# Mixer.net
KiCad netlist of a schematic drawn in Altium Designer
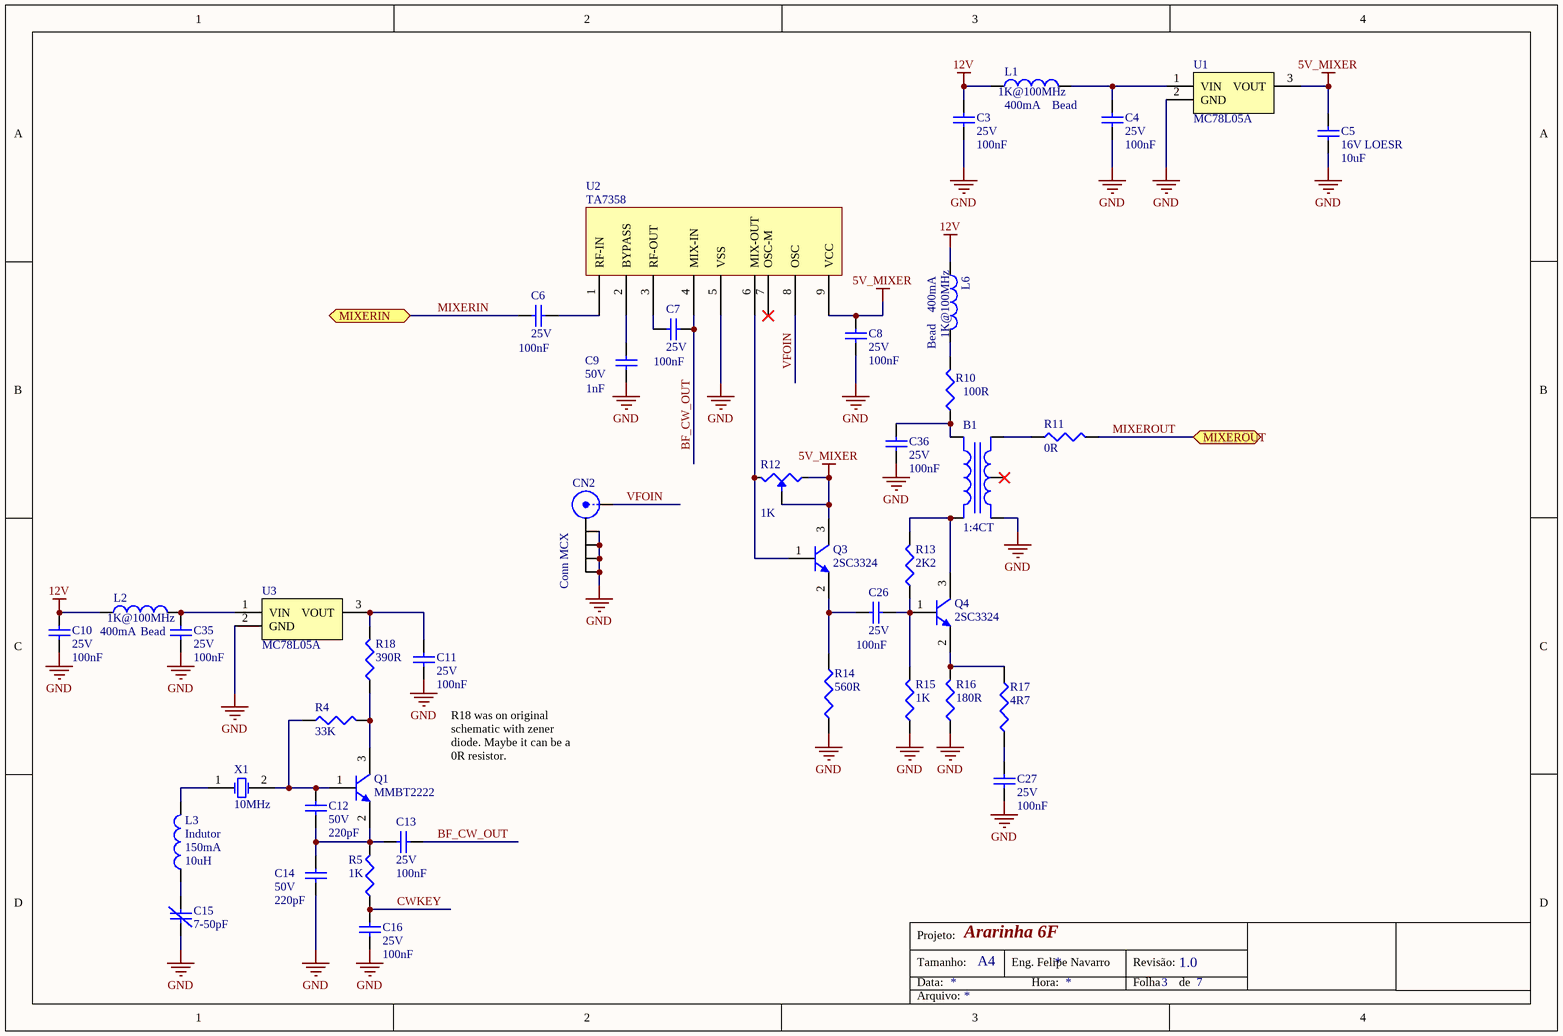
[diagram p0: Mixer.SchDoc]

(export (version "E")
  (design (tool "Eeschema 10.0.6"))
  (components
    (comp (ref "B1")
      (value "1:4CT")
      (footprint "CX2047LANL")
      (description "Balun 4CT:1")
      (libsource (lib "NavarroIND") (part "BALUN CX2047LANL"))
    )
    (comp (ref "C3")
      (value "100nF")
      (footprint "CC0603")
      (description "Capacitor (Semiconductor SIM Model)")
      (fields (field (name "TENSÃO") "25V") (field (name "Comment") "Capacitor Cerâmico"))
      (libsource (lib "NavarroCAP") (part "Cap 100nF 25V 0603 X7R"))
    )
    (comp (ref "C4")
      (value "100nF")
      (footprint "CC0603")
      (description "Capacitor (Semiconductor SIM Model)")
      (fields (field (name "TENSÃO") "25V") (field (name "Comment") "Capacitor Cerâmico"))
      (libsource (lib "NavarroCAP") (part "Cap 100nF 25V 0603 X7R"))
    )
    (comp (ref "C5")
      (value "10uF")
      (footprint "CC0805")
      (description "Capacitor (Semiconductor SIM Model)")
      (fields (field (name "TENSÃO") "16V LOESR") (field (name "Comment") "Capacitor Cerâmico"))
      (libsource (lib "NavarroCAP") (part "Cap 10uF 16V 0805 X6S LOESR"))
    )
    (comp (ref "C6")
      (value "100nF")
      (footprint "CC0603")
      (description "Capacitor (Semiconductor SIM Model)")
      (fields (field (name "TENSÃO") "25V") (field (name "Comment") "Capacitor Cerâmico"))
      (libsource (lib "NavarroCAP") (part "Cap 100nF 25V 0603 X7R"))
    )
    (comp (ref "C7")
      (value "100nF")
      (footprint "CC0603")
      (description "Capacitor (Semiconductor SIM Model)")
      (fields (field (name "TENSÃO") "25V") (field (name "Comment") "Capacitor Cerâmico"))
      (libsource (lib "NavarroCAP") (part "Cap 100nF 25V 0603 X7R"))
    )
    (comp (ref "C8")
      (value "100nF")
      (footprint "CC0603")
      (description "Capacitor (Semiconductor SIM Model)")
      (fields (field (name "TENSÃO") "25V") (field (name "Comment") "Capacitor Cerâmico"))
      (libsource (lib "NavarroCAP") (part "Cap 100nF 25V 0603 X7R"))
    )
    (comp (ref "C9")
      (value "1nF")
      (footprint "CC0603")
      (description "Capacitor (Semiconductor SIM Model)")
      (fields (field (name "TENSÃO") "50V") (field (name "Comment") "Capacitor Cerâmico"))
      (libsource (lib "NavarroCAP") (part "Cap 1nF 50V 0603 NP0"))
    )
    (comp (ref "C10")
      (value "100nF")
      (footprint "CC0603")
      (description "Capacitor (Semiconductor SIM Model)")
      (fields (field (name "TENSÃO") "25V") (field (name "Comment") "Capacitor Cerâmico"))
      (libsource (lib "NavarroCAP") (part "Cap 100nF 25V 0603 X7R"))
    )
    (comp (ref "C11")
      (value "100nF")
      (footprint "CC0603")
      (description "Capacitor (Semiconductor SIM Model)")
      (fields (field (name "TENSÃO") "25V") (field (name "Comment") "Capacitor Cerâmico"))
      (libsource (lib "NavarroCAP") (part "Cap 100nF 25V 0603 X7R"))
    )
    (comp (ref "C12")
      (value "220pF")
      (footprint "CC0603")
      (description "Capacitor (Semiconductor SIM Model)")
      (fields (field (name "TENSÃO") "50V") (field (name "Comment") "Capacitor Cerâmico"))
      (libsource (lib "NavarroCAP") (part "Cap 220pF 50V 0603 NP0"))
    )
    (comp (ref "C13")
      (value "100nF")
      (footprint "CC0603")
      (description "Capacitor (Semiconductor SIM Model)")
      (fields (field (name "TENSÃO") "25V") (field (name "Comment") "Capacitor Cerâmico"))
      (libsource (lib "NavarroCAP") (part "Cap 2.2pf 50V 0603 C0G"))
    )
    (comp (ref "C14")
      (value "220pF")
      (footprint "CC0603")
      (description "Capacitor (Semiconductor SIM Model)")
      (fields (field (name "TENSÃO") "50V") (field (name "Comment") "Capacitor Cerâmico"))
      (libsource (lib "NavarroCAP") (part "Cap 220pF 50V 0603 NP0"))
    )
    (comp (ref "C15")
      (value "7-50pF")
      (footprint "MURATA TZB4")
      (description "Capacitor (Semiconductor SIM Model)")
      (fields (field (name "Comment") "Trimmer"))
      (libsource (lib "NavarroCAP") (part "Trimmer 7-50pF 50V TZB4-BB"))
    )
    (comp (ref "C16")
      (value "100nF")
      (footprint "CC0603")
      (description "Capacitor (Semiconductor SIM Model)")
      (fields (field (name "TENSÃO") "25V") (field (name "Comment") "Capacitor Cerâmico"))
      (libsource (lib "NavarroCAP") (part "Cap 100nF 25V 0603 X7R"))
    )
    (comp (ref "C26")
      (value "100nF")
      (footprint "CC0603")
      (description "Capacitor (Semiconductor SIM Model)")
      (fields (field (name "TENSÃO") "25V") (field (name "Comment") "Capacitor Cerâmico"))
      (libsource (lib "NavarroCAP") (part "Cap 100nF 25V 0603 X7R"))
    )
    (comp (ref "C27")
      (value "100nF")
      (footprint "CC0603")
      (description "Capacitor (Semiconductor SIM Model)")
      (fields (field (name "TENSÃO") "25V") (field (name "Comment") "Capacitor Cerâmico"))
      (libsource (lib "NavarroCAP") (part "Cap 100nF 25V 0603 X7R"))
    )
    (comp (ref "C35")
      (value "100nF")
      (footprint "CC0603")
      (description "Capacitor (Semiconductor SIM Model)")
      (fields (field (name "TENSÃO") "25V") (field (name "Comment") "Capacitor Cerâmico"))
      (libsource (lib "NavarroCAP") (part "Cap 100nF 25V 0603 X7R"))
    )
    (comp (ref "C36")
      (value "100nF")
      (footprint "CC0603")
      (description "Capacitor (Semiconductor SIM Model)")
      (fields (field (name "TENSÃO") "25V") (field (name "Comment") "Capacitor Cerâmico"))
      (libsource (lib "NavarroCAP") (part "Cap 100nF 25V 0603 X7R"))
    )
    (comp (ref "CN2")
      (value "Conn MCX")
      (footprint "CONN MCX MOLEX")
      (description "Conector MCX")
      (libsource (lib "NavarroCON") (part "Conn MCX"))
    )
    (comp (ref "L1")
      (value "Bead")
      (footprint "CC0603")
      (fields (field (name "CORRENTE") "400mA") (field (name "ALTIUM_VALUE") "1K@100MHz"))
      (libsource (lib "NavarroIND") (part "Bd 1K@100MHz 0603 400mA"))
    )
    (comp (ref "L2")
      (value "Bead")
      (footprint "CC0603")
      (fields (field (name "CORRENTE") "400mA") (field (name "ALTIUM_VALUE") "1K@100MHz"))
      (libsource (lib "NavarroIND") (part "Bd 1K@100MHz 0603 400mA"))
    )
    (comp (ref "L3")
      (value "Indutor")
      (footprint "CC0805")
      (description "Inductor")
      (fields (field (name "CORRENTE") "150mA") (field (name "ALTIUM_VALUE") "10uH"))
      (libsource (lib "NavarroIND") (part "Ind 10uH 0805 150mA"))
    )
    (comp (ref "L6")
      (value "Bead")
      (footprint "CC0603")
      (fields (field (name "CORRENTE") "400mA") (field (name "ALTIUM_VALUE") "1K@100MHz"))
      (libsource (lib "NavarroIND") (part "Bd 1K@100MHz 0603 400mA"))
    )
    (comp (ref "Q1")
      (value "MMBT2222")
      (footprint "SOT-23-3N")
      (description "NPN General Purpose Amplifier")
      (libsource (lib "NavarroSEMI") (part "TRS MMBT2222 40V 200mA SOT-23-3N"))
    )
    (comp (ref "Q3")
      (value "2SC3324")
      (footprint "SOT-23-3N")
      (description "NPN General Purpose Amplifier")
      (libsource (lib "NavarroSEMI") (part "TRS 2SC3324 120V 100mA SOT-23-3"))
    )
    (comp (ref "Q4")
      (value "2SC3324")
      (footprint "SOT-23-3N")
      (description "NPN General Purpose Amplifier")
      (libsource (lib "NavarroSEMI") (part "TRS 2SC3324 120V 100mA SOT-23-3"))
    )
    (comp (ref "R4")
      (value "33K")
      (footprint "CC0603")
      (description "Resistor")
      (libsource (lib "NavarroRES") (part "Res 33K 1% 0603 1/10W"))
    )
    (comp (ref "R5")
      (value "1K")
      (footprint "CC0603")
      (description "Resistor")
      (libsource (lib "NavarroRES") (part "Res 1K 1% 0603 1/10W"))
    )
    (comp (ref "R10")
      (value "100R")
      (footprint "CC0805")
      (description "Resistor")
      (libsource (lib "NavarroRES") (part "Res 100R 5% 0805 1/8W"))
    )
    (comp (ref "R11")
      (value "0R")
      (footprint "CC0603~0805")
      (description "Resistor")
      (libsource (lib "NavarroRES") (part "Res 0R 0603 1/10W"))
    )
    (comp (ref "R12")
      (value "1K")
      (footprint "POT")
      (description "Potenciometro")
      (fields (field (name "Comment") "Potenciômetro"))
      (libsource (lib "NavarroRES") (part "Res Pot"))
    )
    (comp (ref "R13")
      (value "2K2")
      (footprint "CC0603")
      (description "Resistor")
      (libsource (lib "NavarroRES") (part "Res 2K2 5% 0603 1/10W"))
    )
    (comp (ref "R14")
      (value "560R")
      (footprint "CC0603")
      (description "Resistor")
      (libsource (lib "NavarroRES") (part "Res 560R 1% 0603 1/10w"))
    )
    (comp (ref "R15")
      (value "1K")
      (footprint "CC0603")
      (description "Resistor")
      (libsource (lib "NavarroRES") (part "Res 1K 1% 0603 1/10W"))
    )
    (comp (ref "R16")
      (value "180R")
      (footprint "CC0603")
      (description "Resistor")
      (libsource (lib "NavarroRES") (part "Res 180R 1% 0603 1/10W"))
    )
    (comp (ref "R17")
      (value "4R7")
      (footprint "CC0603")
      (description "Resistor")
      (libsource (lib "NavarroRES") (part "Res 4R7 1% 0603 1/10W"))
    )
    (comp (ref "R18")
      (value "390R")
      (footprint "CC0603")
      (description "Resistor")
      (libsource (lib "NavarroRES") (part "Res 390R 1% 0603 1/10W"))
    )
    (comp (ref "U1")
      (value "MC78L05A")
      (footprint "SOT-89-3N")
      (description "Regulador Linear 5V")
      (libsource (lib "Navarro") (part "MC78L05"))
    )
    (comp (ref "U2")
      (value "TA7358")
      (footprint "SIP9")
      (description "FM FRONT-END")
      (libsource (lib "Navarro") (part "TA7358"))
    )
    (comp (ref "U3")
      (value "MC78L05A")
      (footprint "SOT-89-3N")
      (description "Regulador Linear 5V")
      (libsource (lib "Navarro") (part "MC78L05"))
    )
    (comp (ref "X1")
      (value "10MHz")
      (footprint "HC/49US")
      (description "Crystal Oscillator")
      (libsource (lib "Navarro") (part "XTAL"))
    )
  )
  (nets
    (net (code "1") (name "/BF_CW_OUT") (class "Default")
      (node (ref "C13") (pin "2") (pinfunction "2_2") (pintype "passive"))
      (node (ref "C7") (pin "1") (pinfunction "1_1") (pintype "passive"))
      (node (ref "U2") (pin "4") (pinfunction "MIX-IN_4") (pintype "passive"))
    )
    (net (code "2") (name "/CWKEY") (class "Default")
      (node (ref "C16") (pin "2") (pinfunction "2_2") (pintype "passive"))
      (node (ref "R5") (pin "1") (pinfunction "1_1") (pintype "passive"))
    )
    (net (code "3") (name "/MIXERIN") (class "Default")
      (node (ref "C6") (pin "2") (pinfunction "2_2") (pintype "passive"))
    )
    (net (code "4") (name "/MIXEROUT") (class "Default")
      (node (ref "R11") (pin "2") (pinfunction "2_2") (pintype "passive"))
    )
    (net (code "5") (name "/VFOIN") (class "Default")
      (node (ref "CN2") (pin "1") (pinfunction "X_1") (pintype "passive"))
      (node (ref "U2") (pin "8") (pinfunction "OSC_8") (pintype "passive"))
    )
    (net (code "6") (name "5V_MIXER") (class "Default")
      (node (ref "C5") (pin "2") (pinfunction "2_2") (pintype "passive"))
      (node (ref "C8") (pin "1") (pinfunction "1_1") (pintype "passive"))
      (node (ref "Q3") (pin "3") (pinfunction "C_3") (pintype "passive"))
      (node (ref "R12") (pin "1") (pinfunction "1_1") (pintype "passive"))
      (node (ref "R12") (pin "2") (pinfunction "TAP_2") (pintype "passive"))
      (node (ref "U1") (pin "3") (pinfunction "VOUT_3") (pintype "power_in"))
      (node (ref "U2") (pin "9") (pinfunction "VCC_9") (pintype "passive"))
    )
    (net (code "7") (name "12V") (class "Default")
      (node (ref "C10") (pin "2") (pinfunction "2_2") (pintype "passive"))
      (node (ref "C3") (pin "1") (pinfunction "1_1") (pintype "passive"))
      (node (ref "L1") (pin "1") (pinfunction "1_1") (pintype "passive"))
      (node (ref "L2") (pin "1") (pinfunction "1_1") (pintype "passive"))
      (node (ref "L6") (pin "1") (pinfunction "1_1") (pintype "passive"))
    )
    (net (code "8") (name "GND") (class "Default")
      (node (ref "B1") (pin "3") (pinfunction "Pri-_3") (pintype "passive"))
      (node (ref "C10") (pin "1") (pinfunction "1_1") (pintype "passive"))
      (node (ref "C11") (pin "1") (pinfunction "1_1") (pintype "passive"))
      (node (ref "C14") (pin "1") (pinfunction "1_1") (pintype "passive"))
      (node (ref "C15") (pin "1") (pinfunction "1_1") (pintype "passive"))
      (node (ref "C16") (pin "1") (pinfunction "1_1") (pintype "passive"))
      (node (ref "C27") (pin "2") (pinfunction "2_2") (pintype "passive"))
      (node (ref "C3") (pin "2") (pinfunction "2_2") (pintype "passive"))
      (node (ref "C35") (pin "1") (pinfunction "1_1") (pintype "passive"))
      (node (ref "C36") (pin "2") (pinfunction "2_2") (pintype "passive"))
      (node (ref "C4") (pin "2") (pinfunction "2_2") (pintype "passive"))
      (node (ref "C5") (pin "1") (pinfunction "1_1") (pintype "passive"))
      (node (ref "C8") (pin "2") (pinfunction "2_2") (pintype "passive"))
      (node (ref "C9") (pin "2") (pinfunction "2_2") (pintype "passive"))
      (node (ref "CN2") (pin "2") (pinfunction "Y_2") (pintype "passive"))
      (node (ref "CN2") (pin "3") (pinfunction "Y_3") (pintype "passive"))
      (node (ref "CN2") (pin "4") (pinfunction "Y_4") (pintype "passive"))
      (node (ref "CN2") (pin "5") (pinfunction "Y_5") (pintype "passive"))
      (node (ref "R14") (pin "1") (pinfunction "1_1") (pintype "passive"))
      (node (ref "R15") (pin "1") (pinfunction "1_1") (pintype "passive"))
      (node (ref "R16") (pin "1") (pinfunction "1_1") (pintype "passive"))
      (node (ref "U1") (pin "2") (pinfunction "GND_2") (pintype "power_in"))
      (node (ref "U2") (pin "5") (pinfunction "VSS_5") (pintype "passive"))
      (node (ref "U3") (pin "2") (pinfunction "GND_2") (pintype "power_in"))
    )
    (net (code "9") (name "Net-(B1-Pri+)") (class "Default")
      (node (ref "B1") (pin "4") (pinfunction "Pri+_4") (pintype "passive"))
      (node (ref "Q4") (pin "3") (pinfunction "C_3") (pintype "passive"))
      (node (ref "R13") (pin "2") (pinfunction "2_2") (pintype "passive"))
    )
    (net (code "10") (name "Net-(B1-Sec+-Pad1)") (class "Default")
      (node (ref "B1") (pin "1") (pinfunction "Sec+_1") (pintype "passive"))
      (node (ref "R11") (pin "1") (pinfunction "1_1") (pintype "passive"))
    )
    (net (code "11") (name "Net-(B1-Sec-)") (class "Default")
      (node (ref "B1") (pin "6") (pinfunction "Sec-_6") (pintype "passive"))
      (node (ref "C36") (pin "1") (pinfunction "1_1") (pintype "passive"))
      (node (ref "R10") (pin "1") (pinfunction "1_1") (pintype "passive"))
    )
    (net (code "12") (name "Net-(C15-Pad2)") (class "Default")
      (node (ref "C15") (pin "2") (pinfunction "2_2") (pintype "passive"))
      (node (ref "L3") (pin "1") (pinfunction "1_1") (pintype "passive"))
    )
    (net (code "13") (name "Net-(C27-Pad1)") (class "Default")
      (node (ref "C27") (pin "1") (pinfunction "1_1") (pintype "passive"))
      (node (ref "R17") (pin "1") (pinfunction "1_1") (pintype "passive"))
    )
    (net (code "14") (name "Net-(L6-Pad2)") (class "Default")
      (node (ref "L6") (pin "2") (pinfunction "2_2") (pintype "passive"))
      (node (ref "R10") (pin "2") (pinfunction "2_2") (pintype "passive"))
    )
    (net (code "15") (name "Net-(Q1-B)") (class "Default")
      (node (ref "C12") (pin "2") (pinfunction "2_2") (pintype "passive"))
      (node (ref "Q1") (pin "1") (pinfunction "B_1") (pintype "passive"))
      (node (ref "R4") (pin "1") (pinfunction "1_1") (pintype "passive"))
      (node (ref "X1") (pin "2") (pinfunction "OSC2_2") (pintype "passive"))
    )
    (net (code "16") (name "Net-(Q1-C)") (class "Default")
      (node (ref "Q1") (pin "3") (pinfunction "C_3") (pintype "passive"))
      (node (ref "R18") (pin "1") (pinfunction "1_1") (pintype "passive"))
      (node (ref "R4") (pin "2") (pinfunction "2_2") (pintype "passive"))
    )
    (net (code "17") (name "Net-(Q1-E)") (class "Default")
      (node (ref "C12") (pin "1") (pinfunction "1_1") (pintype "passive"))
      (node (ref "C13") (pin "1") (pinfunction "1_1") (pintype "passive"))
      (node (ref "C14") (pin "2") (pinfunction "2_2") (pintype "passive"))
      (node (ref "Q1") (pin "2") (pinfunction "E_2") (pintype "passive"))
      (node (ref "R5") (pin "2") (pinfunction "2_2") (pintype "passive"))
    )
    (net (code "18") (name "Net-(Q3-B)") (class "Default")
      (node (ref "Q3") (pin "1") (pinfunction "B_1") (pintype "passive"))
      (node (ref "R12") (pin "3") (pinfunction "3_3") (pintype "passive"))
      (node (ref "U2") (pin "6") (pinfunction "MIX-OUT_6") (pintype "passive"))
    )
    (net (code "19") (name "Net-(Q3-E)") (class "Default")
      (node (ref "C26") (pin "2") (pinfunction "2_2") (pintype "passive"))
      (node (ref "Q3") (pin "2") (pinfunction "E_2") (pintype "passive"))
      (node (ref "R14") (pin "2") (pinfunction "2_2") (pintype "passive"))
    )
    (net (code "20") (name "Net-(Q4-B)") (class "Default")
      (node (ref "C26") (pin "1") (pinfunction "1_1") (pintype "passive"))
      (node (ref "Q4") (pin "1") (pinfunction "B_1") (pintype "passive"))
      (node (ref "R13") (pin "1") (pinfunction "1_1") (pintype "passive"))
      (node (ref "R15") (pin "2") (pinfunction "2_2") (pintype "passive"))
    )
    (net (code "21") (name "Net-(Q4-E)") (class "Default")
      (node (ref "Q4") (pin "2") (pinfunction "E_2") (pintype "passive"))
      (node (ref "R16") (pin "2") (pinfunction "2_2") (pintype "passive"))
      (node (ref "R17") (pin "2") (pinfunction "2_2") (pintype "passive"))
    )
    (net (code "22") (name "Net-(U1-VIN)") (class "Default")
      (node (ref "C4") (pin "1") (pinfunction "1_1") (pintype "passive"))
      (node (ref "L1") (pin "2") (pinfunction "2_2") (pintype "passive"))
      (node (ref "U1") (pin "1") (pinfunction "VIN_1") (pintype "power_in"))
    )
    (net (code "23") (name "Net-(U2-BYPASS)") (class "Default")
      (node (ref "C9") (pin "1") (pinfunction "1_1") (pintype "passive"))
      (node (ref "U2") (pin "2") (pinfunction "BYPASS_2") (pintype "passive"))
    )
    (net (code "24") (name "Net-(U2-RF-IN)") (class "Default")
      (node (ref "C6") (pin "1") (pinfunction "1_1") (pintype "passive"))
      (node (ref "U2") (pin "1") (pinfunction "RF-IN_1") (pintype "passive"))
    )
    (net (code "25") (name "Net-(U2-RF-OUT)") (class "Default")
      (node (ref "C7") (pin "2") (pinfunction "2_2") (pintype "passive"))
      (node (ref "U2") (pin "3") (pinfunction "RF-OUT_3") (pintype "passive"))
    )
    (net (code "26") (name "Net-(U3-VIN)") (class "Default")
      (node (ref "C35") (pin "2") (pinfunction "2_2") (pintype "passive"))
      (node (ref "L2") (pin "2") (pinfunction "2_2") (pintype "passive"))
      (node (ref "U3") (pin "1") (pinfunction "VIN_1") (pintype "power_in"))
    )
    (net (code "27") (name "Net-(U3-VOUT)") (class "Default")
      (node (ref "C11") (pin "2") (pinfunction "2_2") (pintype "passive"))
      (node (ref "R18") (pin "2") (pinfunction "2_2") (pintype "passive"))
      (node (ref "U3") (pin "3") (pinfunction "VOUT_3") (pintype "power_in"))
    )
    (net (code "28") (name "Net-(X1-OSC1)") (class "Default")
      (node (ref "L3") (pin "2") (pinfunction "2_2") (pintype "passive"))
      (node (ref "X1") (pin "1") (pinfunction "OSC1_1") (pintype "passive"))
    )
    (net (code "29") (name "unconnected-(B1-Sec+-Pad2)") (class "Default")
      (node (ref "B1") (pin "2") (pinfunction "Sec+_2") (pintype "passive+no_connect"))
    )
    (net (code "30") (name "unconnected-(U2-OSC-M-Pad7)") (class "Default")
      (node (ref "U2") (pin "7") (pinfunction "OSC-M_7") (pintype "passive+no_connect"))
    )
  )
)
